# SRAM-SPI-FLASH.net
KiCad netlist of a schematic drawn in Altium Designer
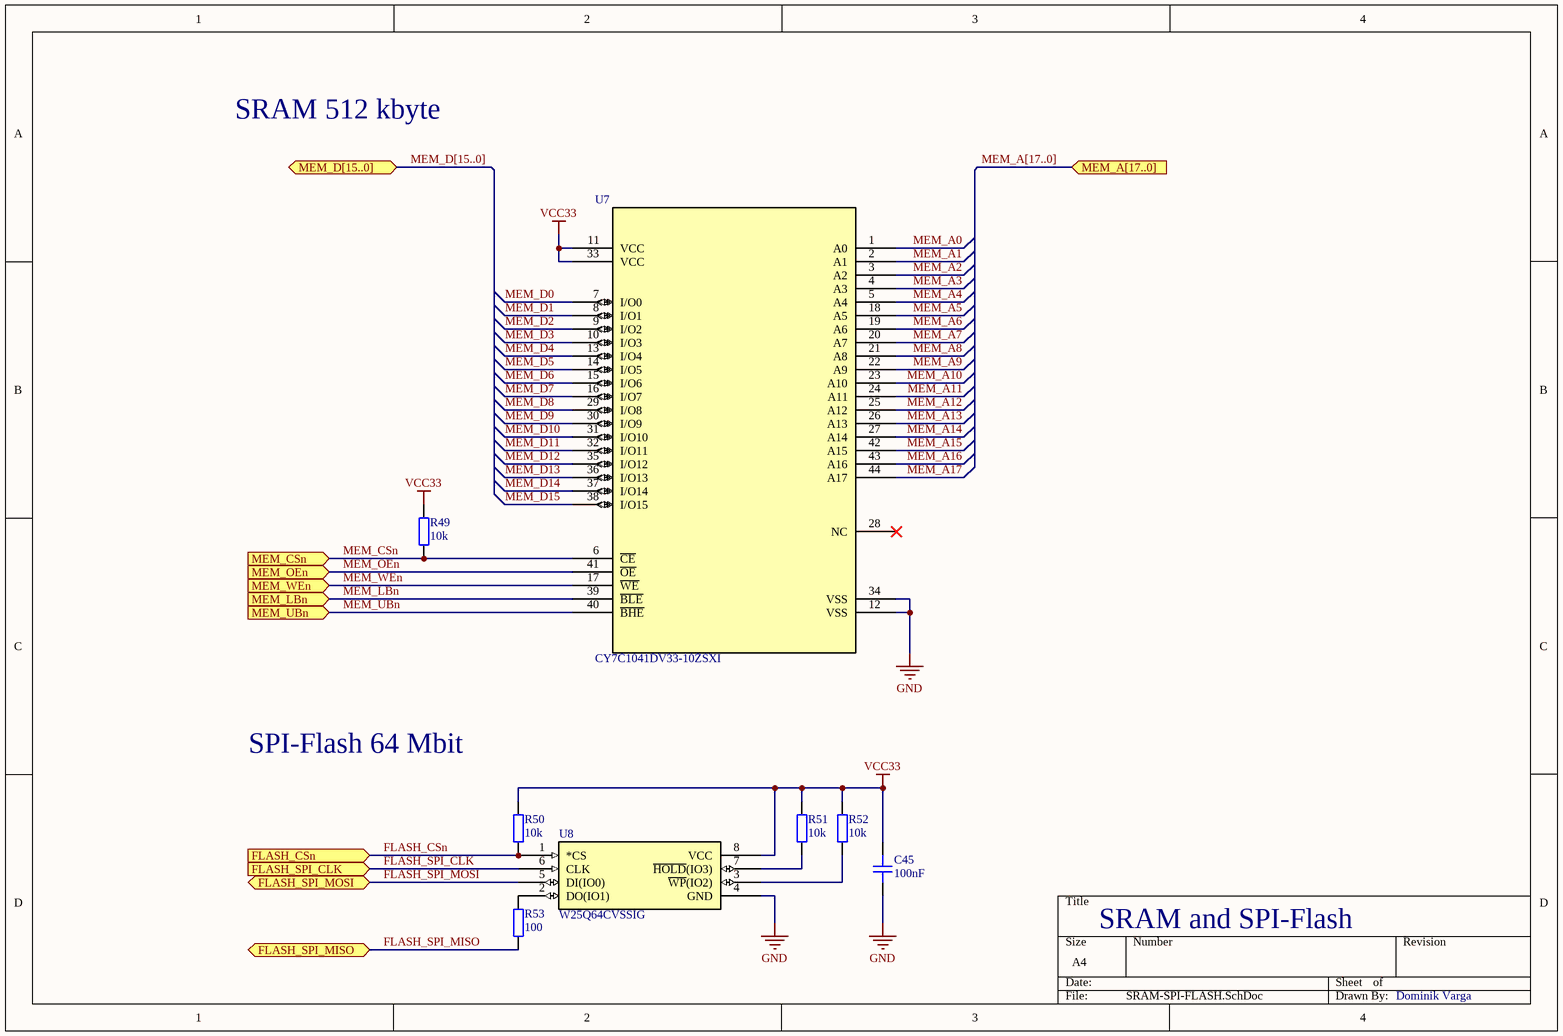
[diagram p0: SRAM-SPI-FLASH.SchDoc]

(export (version "E")
  (design (tool "Eeschema 10.0.6"))
  (components
    (comp (ref "C45")
      (value "100nF")
      (footprint "CAP_SMD0603")
      (description "Capacitor SMD 0603")
      (libsource (lib "NES-Components") (part "CAP_0603"))
    )
    (comp (ref "R49")
      (value "10k")
      (footprint "RES_SMD0603")
      (description "Resistor SMD 0603")
      (libsource (lib "NES-Components") (part "RES_0603"))
    )
    (comp (ref "R50")
      (value "10k")
      (footprint "RES_SMD0603")
      (description "Resistor SMD 0603")
      (libsource (lib "NES-Components") (part "RES_0603"))
    )
    (comp (ref "R51")
      (value "10k")
      (footprint "RES_SMD0603")
      (description "Resistor SMD 0603")
      (libsource (lib "NES-Components") (part "RES_0603"))
    )
    (comp (ref "R52")
      (value "10k")
      (footprint "RES_SMD0603")
      (description "Resistor SMD 0603")
      (libsource (lib "NES-Components") (part "RES_0603"))
    )
    (comp (ref "R53")
      (value "100")
      (footprint "RES_SMD0603")
      (description "Resistor SMD 0603")
      (libsource (lib "NES-Components") (part "RES_0603"))
    )
    (comp (ref "U7")
      (value "CY7C1041DV33-10ZSXI")
      (footprint "SOP80P1184X119-44N")
      (description "SRAM Chip Asynchronous Single 3.3V 4M-Bit 256K x 16 10ns 44-Pin TSOP-II Tray")
      (fields (field (name "COPYRIGHT") "Copyright (C) 2023 Ultra Librarian. All rights reserved."))
      (libsource (lib "NES-Components") (part "CY7C1041DV33-10ZSXI"))
    )
    (comp (ref "U8")
      (value "W25Q64CVSSIG")
      (footprint "SOIC127P790X216-8N")
      (description "SERIAL FLASH MEMORY WITH   DUAL AND QUAD SPI")
      (fields (field (name "COPYRIGHT") "Copyright (C) 2023 Ultra Librarian. All rights reserved."))
      (libsource (lib "NES-Components") (part "W25Q64CVSSIG"))
    )
  )
  (nets
    (net (code "1") (name "/FLASH_CSn") (class "Default")
      (node (ref "R50") (pin "1") (pinfunction "1_1") (pintype "passive"))
      (node (ref "U8") (pin "1") (pinfunction "*CS_1") (pintype "input"))
    )
    (net (code "2") (name "/FLASH_SPI_CLK") (class "Default")
      (node (ref "U8") (pin "6") (pinfunction "CLK_6") (pintype "input"))
    )
    (net (code "3") (name "/FLASH_SPI_MISO") (class "Default")
      (node (ref "R53") (pin "1") (pinfunction "1_1") (pintype "passive"))
    )
    (net (code "4") (name "/FLASH_SPI_MOSI") (class "Default")
      (node (ref "U8") (pin "5") (pinfunction "DI(IO0)_5") (pintype "bidirectional"))
    )
    (net (code "5") (name "/MEM_A0") (class "Default")
      (node (ref "U7") (pin "1") (pinfunction "A0_1") (pintype "passive"))
    )
    (net (code "6") (name "/MEM_A1") (class "Default")
      (node (ref "U7") (pin "2") (pinfunction "A1_2") (pintype "passive"))
    )
    (net (code "7") (name "/MEM_A2") (class "Default")
      (node (ref "U7") (pin "3") (pinfunction "A2_3") (pintype "passive"))
    )
    (net (code "8") (name "/MEM_A3") (class "Default")
      (node (ref "U7") (pin "4") (pinfunction "A3_4") (pintype "passive"))
    )
    (net (code "9") (name "/MEM_A4") (class "Default")
      (node (ref "U7") (pin "5") (pinfunction "A4_5") (pintype "passive"))
    )
    (net (code "10") (name "/MEM_A5") (class "Default")
      (node (ref "U7") (pin "18") (pinfunction "A5_18") (pintype "passive"))
    )
    (net (code "11") (name "/MEM_A6") (class "Default")
      (node (ref "U7") (pin "19") (pinfunction "A6_19") (pintype "passive"))
    )
    (net (code "12") (name "/MEM_A7") (class "Default")
      (node (ref "U7") (pin "20") (pinfunction "A7_20") (pintype "passive"))
    )
    (net (code "13") (name "/MEM_A8") (class "Default")
      (node (ref "U7") (pin "21") (pinfunction "A8_21") (pintype "passive"))
    )
    (net (code "14") (name "/MEM_A9") (class "Default")
      (node (ref "U7") (pin "22") (pinfunction "A9_22") (pintype "passive"))
    )
    (net (code "15") (name "/MEM_A10") (class "Default")
      (node (ref "U7") (pin "23") (pinfunction "A10_23") (pintype "passive"))
    )
    (net (code "16") (name "/MEM_A11") (class "Default")
      (node (ref "U7") (pin "24") (pinfunction "A11_24") (pintype "passive"))
    )
    (net (code "17") (name "/MEM_A12") (class "Default")
      (node (ref "U7") (pin "25") (pinfunction "A12_25") (pintype "passive"))
    )
    (net (code "18") (name "/MEM_A13") (class "Default")
      (node (ref "U7") (pin "26") (pinfunction "A13_26") (pintype "passive"))
    )
    (net (code "19") (name "/MEM_A14") (class "Default")
      (node (ref "U7") (pin "27") (pinfunction "A14_27") (pintype "passive"))
    )
    (net (code "20") (name "/MEM_A15") (class "Default")
      (node (ref "U7") (pin "42") (pinfunction "A15_42") (pintype "passive"))
    )
    (net (code "21") (name "/MEM_A16") (class "Default")
      (node (ref "U7") (pin "43") (pinfunction "A16_43") (pintype "passive"))
    )
    (net (code "22") (name "/MEM_A17") (class "Default")
      (node (ref "U7") (pin "44") (pinfunction "A17_44") (pintype "passive"))
    )
    (net (code "24") (name "/MEM_CSn") (class "Default")
      (node (ref "R49") (pin "1") (pinfunction "1_1") (pintype "passive"))
      (node (ref "U7") (pin "6") (pinfunction "~{CE}_6") (pintype "passive"))
    )
    (net (code "25") (name "/MEM_D0") (class "Default")
      (node (ref "U7") (pin "7") (pinfunction "I/O0_7") (pintype "bidirectional"))
    )
    (net (code "26") (name "/MEM_D1") (class "Default")
      (node (ref "U7") (pin "8") (pinfunction "I/O1_8") (pintype "bidirectional"))
    )
    (net (code "27") (name "/MEM_D2") (class "Default")
      (node (ref "U7") (pin "9") (pinfunction "I/O2_9") (pintype "bidirectional"))
    )
    (net (code "28") (name "/MEM_D3") (class "Default")
      (node (ref "U7") (pin "10") (pinfunction "I/O3_10") (pintype "bidirectional"))
    )
    (net (code "29") (name "/MEM_D4") (class "Default")
      (node (ref "U7") (pin "13") (pinfunction "I/O4_13") (pintype "bidirectional"))
    )
    (net (code "30") (name "/MEM_D5") (class "Default")
      (node (ref "U7") (pin "14") (pinfunction "I/O5_14") (pintype "bidirectional"))
    )
    (net (code "31") (name "/MEM_D6") (class "Default")
      (node (ref "U7") (pin "15") (pinfunction "I/O6_15") (pintype "bidirectional"))
    )
    (net (code "32") (name "/MEM_D7") (class "Default")
      (node (ref "U7") (pin "16") (pinfunction "I/O7_16") (pintype "bidirectional"))
    )
    (net (code "33") (name "/MEM_D8") (class "Default")
      (node (ref "U7") (pin "29") (pinfunction "I/O8_29") (pintype "bidirectional"))
    )
    (net (code "34") (name "/MEM_D9") (class "Default")
      (node (ref "U7") (pin "30") (pinfunction "I/O9_30") (pintype "bidirectional"))
    )
    (net (code "35") (name "/MEM_D10") (class "Default")
      (node (ref "U7") (pin "31") (pinfunction "I/O10_31") (pintype "bidirectional"))
    )
    (net (code "36") (name "/MEM_D11") (class "Default")
      (node (ref "U7") (pin "32") (pinfunction "I/O11_32") (pintype "bidirectional"))
    )
    (net (code "37") (name "/MEM_D12") (class "Default")
      (node (ref "U7") (pin "35") (pinfunction "I/O12_35") (pintype "bidirectional"))
    )
    (net (code "38") (name "/MEM_D13") (class "Default")
      (node (ref "U7") (pin "36") (pinfunction "I/O13_36") (pintype "bidirectional"))
    )
    (net (code "39") (name "/MEM_D14") (class "Default")
      (node (ref "U7") (pin "37") (pinfunction "I/O14_37") (pintype "bidirectional"))
    )
    (net (code "40") (name "/MEM_D15") (class "Default")
      (node (ref "U7") (pin "38") (pinfunction "I/O15_38") (pintype "bidirectional"))
    )
    (net (code "42") (name "/MEM_LBn") (class "Default")
      (node (ref "U7") (pin "39") (pinfunction "~{BLE}_39") (pintype "passive"))
    )
    (net (code "43") (name "/MEM_OEn") (class "Default")
      (node (ref "U7") (pin "41") (pinfunction "~{OE}_41") (pintype "passive"))
    )
    (net (code "44") (name "/MEM_UBn") (class "Default")
      (node (ref "U7") (pin "40") (pinfunction "~{BHE}_40") (pintype "passive"))
    )
    (net (code "45") (name "/MEM_WEn") (class "Default")
      (node (ref "U7") (pin "17") (pinfunction "~{WE}_17") (pintype "passive"))
    )
    (net (code "46") (name "GND") (class "Default")
      (node (ref "C45") (pin "1") (pinfunction "1_1") (pintype "passive"))
      (node (ref "U7") (pin "12") (pinfunction "VSS_12") (pintype "power_in"))
      (node (ref "U7") (pin "34") (pinfunction "VSS_34") (pintype "power_in"))
      (node (ref "U8") (pin "4") (pinfunction "GND_4") (pintype "power_in"))
    )
    (net (code "47") (name "Net-(U8-DO(IO1))") (class "Default")
      (node (ref "R53") (pin "2") (pinfunction "2_2") (pintype "passive"))
      (node (ref "U8") (pin "2") (pinfunction "DO(IO1)_2") (pintype "bidirectional"))
    )
    (net (code "48") (name "Net-(U8-~{HOLD}(IO3))") (class "Default")
      (node (ref "R51") (pin "1") (pinfunction "1_1") (pintype "passive"))
      (node (ref "U8") (pin "7") (pinfunction "~{HOLD}(IO3)_7") (pintype "bidirectional"))
    )
    (net (code "49") (name "Net-(U8-~{WP}(IO2))") (class "Default")
      (node (ref "R52") (pin "1") (pinfunction "1_1") (pintype "passive"))
      (node (ref "U8") (pin "3") (pinfunction "~{WP}(IO2)_3") (pintype "bidirectional"))
    )
    (net (code "50") (name "VCC33") (class "Default")
      (node (ref "C45") (pin "2") (pinfunction "2_2") (pintype "passive"))
      (node (ref "R49") (pin "2") (pinfunction "2_2") (pintype "passive"))
      (node (ref "R50") (pin "2") (pinfunction "2_2") (pintype "passive"))
      (node (ref "R51") (pin "2") (pinfunction "2_2") (pintype "passive"))
      (node (ref "R52") (pin "2") (pinfunction "2_2") (pintype "passive"))
      (node (ref "U7") (pin "11") (pinfunction "VCC_11") (pintype "power_in"))
      (node (ref "U7") (pin "33") (pinfunction "VCC_33") (pintype "power_in"))
      (node (ref "U8") (pin "8") (pinfunction "VCC_8") (pintype "power_in"))
    )
    (net (code "51") (name "unconnected-(U7-NC-Pad28)") (class "Default")
      (node (ref "U7") (pin "28") (pinfunction "NC_28") (pintype "passive+no_connect"))
    )
  )
)
